# phim_led.net
KiCad netlist of a schematic drawn in Altium Designer
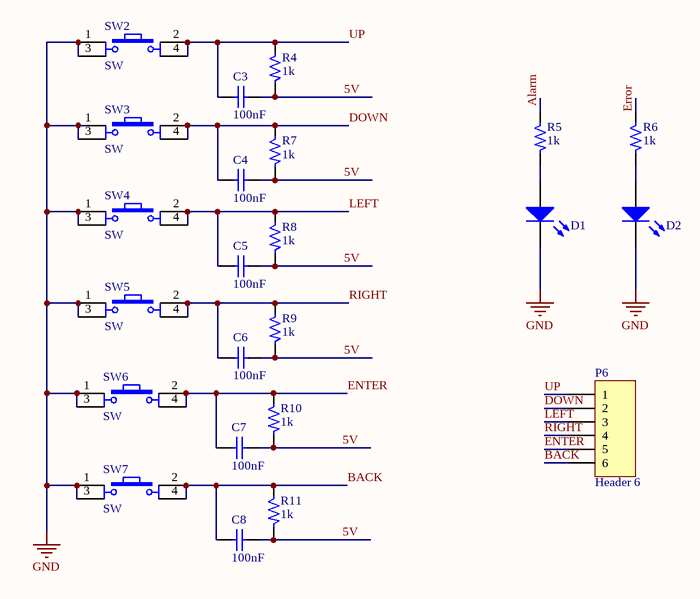
[diagram p0: phim_led.SchDoc]

(export (version "E")
  (design (tool "Eeschema 10.0.6"))
  (components
    (comp (ref "C3")
      (value "100nF")
      (footprint "Tu-pico")
      (description "Capacitor")
      (fields (field (name "Comment") "Capacitor Ceramic") (field (name "PUBLISHER") "Altium Limited"))
      (libsource (lib "My Library") (part "CapCeramic"))
    )
    (comp (ref "C4")
      (value "100nF")
      (footprint "Tu-pico")
      (description "Capacitor")
      (fields (field (name "Comment") "Capacitor Ceramic") (field (name "PUBLISHER") "Altium Limited"))
      (libsource (lib "My Library") (part "CapCeramic"))
    )
    (comp (ref "C5")
      (value "100nF")
      (footprint "Tu-pico")
      (description "Capacitor")
      (fields (field (name "Comment") "Capacitor Ceramic") (field (name "PUBLISHER") "Altium Limited"))
      (libsource (lib "My Library") (part "CapCeramic"))
    )
    (comp (ref "C6")
      (value "100nF")
      (footprint "Tu-pico")
      (description "Capacitor")
      (fields (field (name "Comment") "Capacitor Ceramic") (field (name "PUBLISHER") "Altium Limited"))
      (libsource (lib "My Library") (part "CapCeramic"))
    )
    (comp (ref "C7")
      (value "100nF")
      (footprint "Tu-pico")
      (description "Capacitor")
      (fields (field (name "Comment") "Capacitor Ceramic") (field (name "PUBLISHER") "Altium Limited"))
      (libsource (lib "My Library") (part "CapCeramic"))
    )
    (comp (ref "C8")
      (value "100nF")
      (footprint "Tu-pico")
      (description "Capacitor")
      (fields (field (name "Comment") "Capacitor Ceramic") (field (name "PUBLISHER") "Altium Limited"))
      (libsource (lib "My Library") (part "CapCeramic"))
    )
    (comp (ref "D1")
      (value "LED")
      (footprint "MinhTien_PcbLib:LED_3mm")
      (description "Typical INFRARED GaAs LED")
      (fields (field (name "PUBLISHER") "Altium Limited"))
      (libsource (lib "MinhTien_SCHLib") (part "LED"))
    )
    (comp (ref "D2")
      (value "LED")
      (footprint "MinhTien_PcbLib:LED_3mm")
      (description "Typical INFRARED GaAs LED")
      (fields (field (name "PUBLISHER") "Altium Limited"))
      (libsource (lib "MinhTien_SCHLib") (part "LED"))
    )
    (comp (ref "P6")
      (value "Header 6")
      (footprint "HDR1X6")
      (description "Header, 6-Pin")
      (fields (field (name "PUBLISHER") "Altium Limited"))
      (libsource (lib "My Library") (part "Header 6"))
    )
    (comp (ref "R4")
      (value "1k")
      (footprint "RES-1/4W")
      (description "Resistor 1/4W")
      (libsource (lib "syhaunguyen") (part "R"))
    )
    (comp (ref "R5")
      (value "1k")
      (footprint "RES-1/4W")
      (description "Resistor 1/4W")
      (libsource (lib "syhaunguyen") (part "R"))
    )
    (comp (ref "R6")
      (value "1k")
      (footprint "RES-1/4W")
      (description "Resistor 1/4W")
      (libsource (lib "syhaunguyen") (part "R"))
    )
    (comp (ref "R7")
      (value "1k")
      (footprint "RES-1/4W")
      (description "Resistor 1/4W")
      (libsource (lib "syhaunguyen") (part "R"))
    )
    (comp (ref "R8")
      (value "1k")
      (footprint "RES-1/4W")
      (description "Resistor 1/4W")
      (libsource (lib "syhaunguyen") (part "R"))
    )
    (comp (ref "R9")
      (value "1k")
      (footprint "RES-1/4W")
      (description "Resistor 1/4W")
      (libsource (lib "syhaunguyen") (part "R"))
    )
    (comp (ref "R10")
      (value "1k")
      (footprint "RES-1/4W")
      (description "Resistor 1/4W")
      (libsource (lib "syhaunguyen") (part "R"))
    )
    (comp (ref "R11")
      (value "1k")
      (footprint "RES-1/4W")
      (description "Resistor 1/4W")
      (libsource (lib "syhaunguyen") (part "R"))
    )
    (comp (ref "SW2")
      (value "SW")
      (footprint "SW4")
      (description "Switch button 4 pin")
      (libsource (lib "My Library") (part "SW4"))
    )
    (comp (ref "SW3")
      (value "SW")
      (footprint "SW4")
      (description "Switch button 4 pin")
      (libsource (lib "My Library") (part "SW4"))
    )
    (comp (ref "SW4")
      (value "SW")
      (footprint "SW4")
      (description "Switch button 4 pin")
      (libsource (lib "My Library") (part "SW4"))
    )
    (comp (ref "SW5")
      (value "SW")
      (footprint "SW4")
      (description "Switch button 4 pin")
      (libsource (lib "My Library") (part "SW4"))
    )
    (comp (ref "SW6")
      (value "SW")
      (footprint "SW4")
      (description "Switch button 4 pin")
      (libsource (lib "My Library") (part "SW4"))
    )
    (comp (ref "SW7")
      (value "SW")
      (footprint "SW4")
      (description "Switch button 4 pin")
      (libsource (lib "My Library") (part "SW4"))
    )
  )
  (nets
    (net (code "1") (name "/5V") (class "Default")
      (node (ref "C3") (pin "2") (pinfunction "2_2") (pintype "passive"))
      (node (ref "C4") (pin "2") (pinfunction "2_2") (pintype "passive"))
      (node (ref "C5") (pin "2") (pinfunction "2_2") (pintype "passive"))
      (node (ref "C6") (pin "2") (pinfunction "2_2") (pintype "passive"))
      (node (ref "C7") (pin "2") (pinfunction "2_2") (pintype "passive"))
      (node (ref "C8") (pin "2") (pinfunction "2_2") (pintype "passive"))
      (node (ref "R10") (pin "2") (pinfunction "2_2") (pintype "passive"))
      (node (ref "R11") (pin "2") (pinfunction "2_2") (pintype "passive"))
      (node (ref "R4") (pin "2") (pinfunction "2_2") (pintype "passive"))
      (node (ref "R7") (pin "2") (pinfunction "2_2") (pintype "passive"))
      (node (ref "R8") (pin "2") (pinfunction "2_2") (pintype "passive"))
      (node (ref "R9") (pin "2") (pinfunction "2_2") (pintype "passive"))
    )
    (net (code "2") (name "/Alarm") (class "Default")
      (node (ref "R5") (pin "1") (pinfunction "1_1") (pintype "passive"))
    )
    (net (code "3") (name "/BACK") (class "Default")
      (node (ref "C8") (pin "1") (pinfunction "1_1") (pintype "passive"))
      (node (ref "P6") (pin "6") (pinfunction "6_6") (pintype "passive"))
      (node (ref "R11") (pin "1") (pinfunction "1_1") (pintype "passive"))
      (node (ref "SW7") (pin "2") (pintype "passive"))
      (node (ref "SW7") (pin "4") (pintype "passive"))
    )
    (net (code "4") (name "/DOWN") (class "Default")
      (node (ref "C4") (pin "1") (pinfunction "1_1") (pintype "passive"))
      (node (ref "P6") (pin "2") (pinfunction "2_2") (pintype "passive"))
      (node (ref "R7") (pin "1") (pinfunction "1_1") (pintype "passive"))
      (node (ref "SW3") (pin "2") (pintype "passive"))
      (node (ref "SW3") (pin "4") (pintype "passive"))
    )
    (net (code "5") (name "/ENTER") (class "Default")
      (node (ref "C7") (pin "1") (pinfunction "1_1") (pintype "passive"))
      (node (ref "P6") (pin "5") (pinfunction "5_5") (pintype "passive"))
      (node (ref "R10") (pin "1") (pinfunction "1_1") (pintype "passive"))
      (node (ref "SW6") (pin "2") (pintype "passive"))
      (node (ref "SW6") (pin "4") (pintype "passive"))
    )
    (net (code "6") (name "/Error") (class "Default")
      (node (ref "R6") (pin "1") (pinfunction "1_1") (pintype "passive"))
    )
    (net (code "7") (name "/LEFT") (class "Default")
      (node (ref "C5") (pin "1") (pinfunction "1_1") (pintype "passive"))
      (node (ref "P6") (pin "3") (pinfunction "3_3") (pintype "passive"))
      (node (ref "R8") (pin "1") (pinfunction "1_1") (pintype "passive"))
      (node (ref "SW4") (pin "2") (pintype "passive"))
      (node (ref "SW4") (pin "4") (pintype "passive"))
    )
    (net (code "8") (name "/RIGHT") (class "Default")
      (node (ref "C6") (pin "1") (pinfunction "1_1") (pintype "passive"))
      (node (ref "P6") (pin "4") (pinfunction "4_4") (pintype "passive"))
      (node (ref "R9") (pin "1") (pinfunction "1_1") (pintype "passive"))
      (node (ref "SW5") (pin "2") (pintype "passive"))
      (node (ref "SW5") (pin "4") (pintype "passive"))
    )
    (net (code "9") (name "/UP") (class "Default")
      (node (ref "C3") (pin "1") (pinfunction "1_1") (pintype "passive"))
      (node (ref "P6") (pin "1") (pinfunction "1_1") (pintype "passive"))
      (node (ref "R4") (pin "1") (pinfunction "1_1") (pintype "passive"))
      (node (ref "SW2") (pin "2") (pintype "passive"))
      (node (ref "SW2") (pin "4") (pintype "passive"))
    )
    (net (code "10") (name "GND") (class "Default")
      (node (ref "D1") (pin "2") (pinfunction "K_2") (pintype "passive"))
      (node (ref "D2") (pin "2") (pinfunction "K_2") (pintype "passive"))
      (node (ref "SW2") (pin "1") (pintype "passive"))
      (node (ref "SW2") (pin "3") (pintype "passive"))
      (node (ref "SW3") (pin "1") (pintype "passive"))
      (node (ref "SW3") (pin "3") (pintype "passive"))
      (node (ref "SW4") (pin "1") (pintype "passive"))
      (node (ref "SW4") (pin "3") (pintype "passive"))
      (node (ref "SW5") (pin "1") (pintype "passive"))
      (node (ref "SW5") (pin "3") (pintype "passive"))
      (node (ref "SW6") (pin "1") (pintype "passive"))
      (node (ref "SW6") (pin "3") (pintype "passive"))
      (node (ref "SW7") (pin "1") (pintype "passive"))
      (node (ref "SW7") (pin "3") (pintype "passive"))
    )
    (net (code "11") (name "Net-(D1-A)") (class "Default")
      (node (ref "D1") (pin "1") (pinfunction "A_1") (pintype "passive"))
      (node (ref "R5") (pin "2") (pinfunction "2_2") (pintype "passive"))
    )
    (net (code "12") (name "Net-(D2-A)") (class "Default")
      (node (ref "D2") (pin "1") (pinfunction "A_1") (pintype "passive"))
      (node (ref "R6") (pin "2") (pinfunction "2_2") (pintype "passive"))
    )
  )
)
